# lsm6dso-breakout.net
KiCad netlist of a schematic drawn in EAGLE
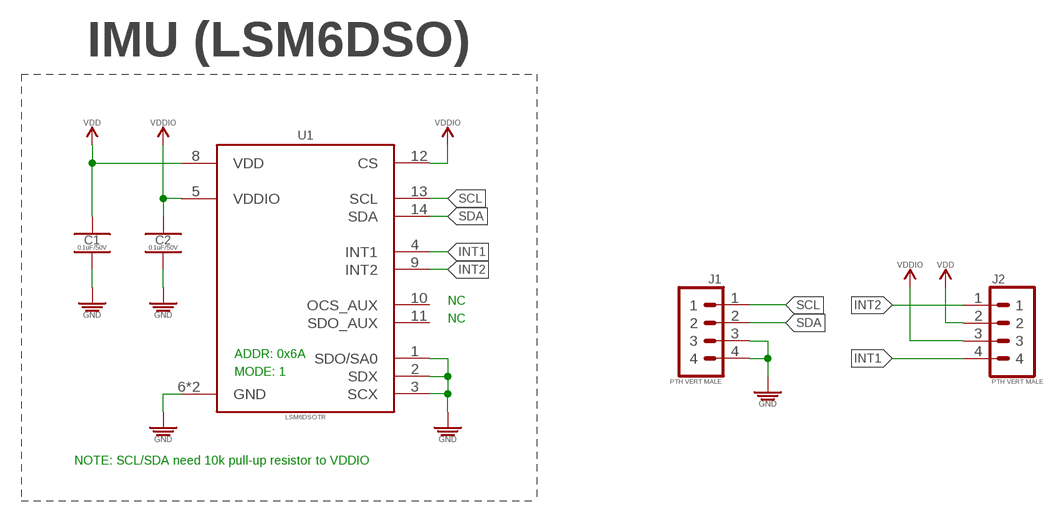
[diagram p0: schematic, sheet 1]

(export (version "E")
  (design (tool "Eeschema 10.0.6"))
  (components
    (comp (ref "C1")
      (value "0.1uF/50V")
      (footprint "eagle-import:CAPC1005X55_SMD-0402")
      (fields (field (name "MFR") "TDK Corporation") (field (name "MPN") "C1005X7R1H104K050BE"))
      (libsource (lib "eagle-import") (part "0.1UF_SMD-0402_50V-10%"))
    )
    (comp (ref "C2")
      (value "0.1uF/50V")
      (footprint "eagle-import:CAPC1005X55_SMD-0402")
      (fields (field (name "MFR") "TDK Corporation") (field (name "MPN") "C1005X7R1H104K050BE"))
      (libsource (lib "eagle-import") (part "0.1UF_SMD-0402_50V-10%"))
    )
    (comp (ref "J1")
      (value "PTH VERT MALE")
      (footprint "eagle-import:HDRV4W64P254_1X4_1016X254X838B")
      (fields (field (name "MFR") "Sullins Connector Solutions") (field (name "MPN") "PEC04SAAN"))
      (libsource (lib "eagle-import") (part "1X04_PTH_VERT_MALE_2.54MM"))
    )
    (comp (ref "J2")
      (value "PTH VERT MALE")
      (footprint "eagle-import:HDRV4W64P254_1X4_1016X254X838B")
      (fields (field (name "MFR") "Sullins Connector Solutions") (field (name "MPN") "PEC04SAAN"))
      (libsource (lib "eagle-import") (part "1X04_PTH_VERT_MALE_2.54MM"))
    )
    (comp (ref "U1")
      (value "LSM6DSOTR")
      (footprint "eagle-import:QFN50P250X300X86-14N")
      (fields (field (name "MFR") "STMicroelectronics"))
      (libsource (lib "eagle-import") (part "LSMDSO"))
    )
  )
  (nets
    (net (code "1") (name "GND") (class "Default")
      (node (ref "C1") (pin "2") (pinfunction "2_2") (pintype "passive"))
      (node (ref "C2") (pin "2") (pinfunction "2_2") (pintype "passive"))
      (node (ref "J1") (pin "3") (pinfunction "3_3") (pintype "passive"))
      (node (ref "J1") (pin "4") (pinfunction "4_4") (pintype "passive"))
      (node (ref "U1") (pin "1") (pinfunction "SDO/SA0_1") (pintype "bidirectional"))
      (node (ref "U1") (pin "2") (pinfunction "SDX_2") (pintype "bidirectional"))
      (node (ref "U1") (pin "3") (pinfunction "SCX_3") (pintype "bidirectional"))
      (node (ref "U1") (pin "6") (pinfunction "GND_6") (pintype "power_in"))
      (node (ref "U1") (pin "7") (pinfunction "GND_7") (pintype "power_in"))
    )
    (net (code "2") (name "INT1") (class "Default")
      (node (ref "J2") (pin "4") (pinfunction "4_4") (pintype "passive"))
      (node (ref "U1") (pin "4") (pinfunction "INT1_4") (pintype "bidirectional"))
    )
    (net (code "3") (name "INT2") (class "Default")
      (node (ref "J2") (pin "1") (pinfunction "1_1") (pintype "passive"))
      (node (ref "U1") (pin "9") (pinfunction "INT2_9") (pintype "bidirectional"))
    )
    (net (code "4") (name "SCL") (class "Default")
      (node (ref "J1") (pin "1") (pinfunction "1_1") (pintype "passive"))
      (node (ref "U1") (pin "13") (pinfunction "SCL_13") (pintype "bidirectional"))
    )
    (net (code "5") (name "SDA") (class "Default")
      (node (ref "J1") (pin "2") (pinfunction "2_2") (pintype "passive"))
      (node (ref "U1") (pin "14") (pinfunction "SDA_14") (pintype "bidirectional"))
    )
    (net (code "6") (name "VDD") (class "Default")
      (node (ref "C1") (pin "1") (pinfunction "1_1") (pintype "passive"))
      (node (ref "J2") (pin "2") (pinfunction "2_2") (pintype "passive"))
      (node (ref "U1") (pin "8") (pinfunction "VDD_8") (pintype "power_in"))
    )
    (net (code "7") (name "VDDIO") (class "Default")
      (node (ref "C2") (pin "1") (pinfunction "1_1") (pintype "passive"))
      (node (ref "J2") (pin "3") (pinfunction "3_3") (pintype "passive"))
      (node (ref "U1") (pin "12") (pinfunction "CS_12") (pintype "bidirectional"))
      (node (ref "U1") (pin "5") (pinfunction "VDDIO_5") (pintype "power_in"))
    )
    (net (code "8") (name "unconnected-(U1-OCS_AUX-Pad10)") (class "Default")
      (node (ref "U1") (pin "10") (pinfunction "OCS_AUX_10") (pintype "bidirectional"))
    )
    (net (code "9") (name "unconnected-(U1-SDO_AUX-Pad11)") (class "Default")
      (node (ref "U1") (pin "11") (pinfunction "SDO_AUX_11") (pintype "bidirectional"))
    )
  )
)
